# STRWL-S04-V00-Microcontroller.net
KiCad netlist of a schematic drawn in Altium Designer
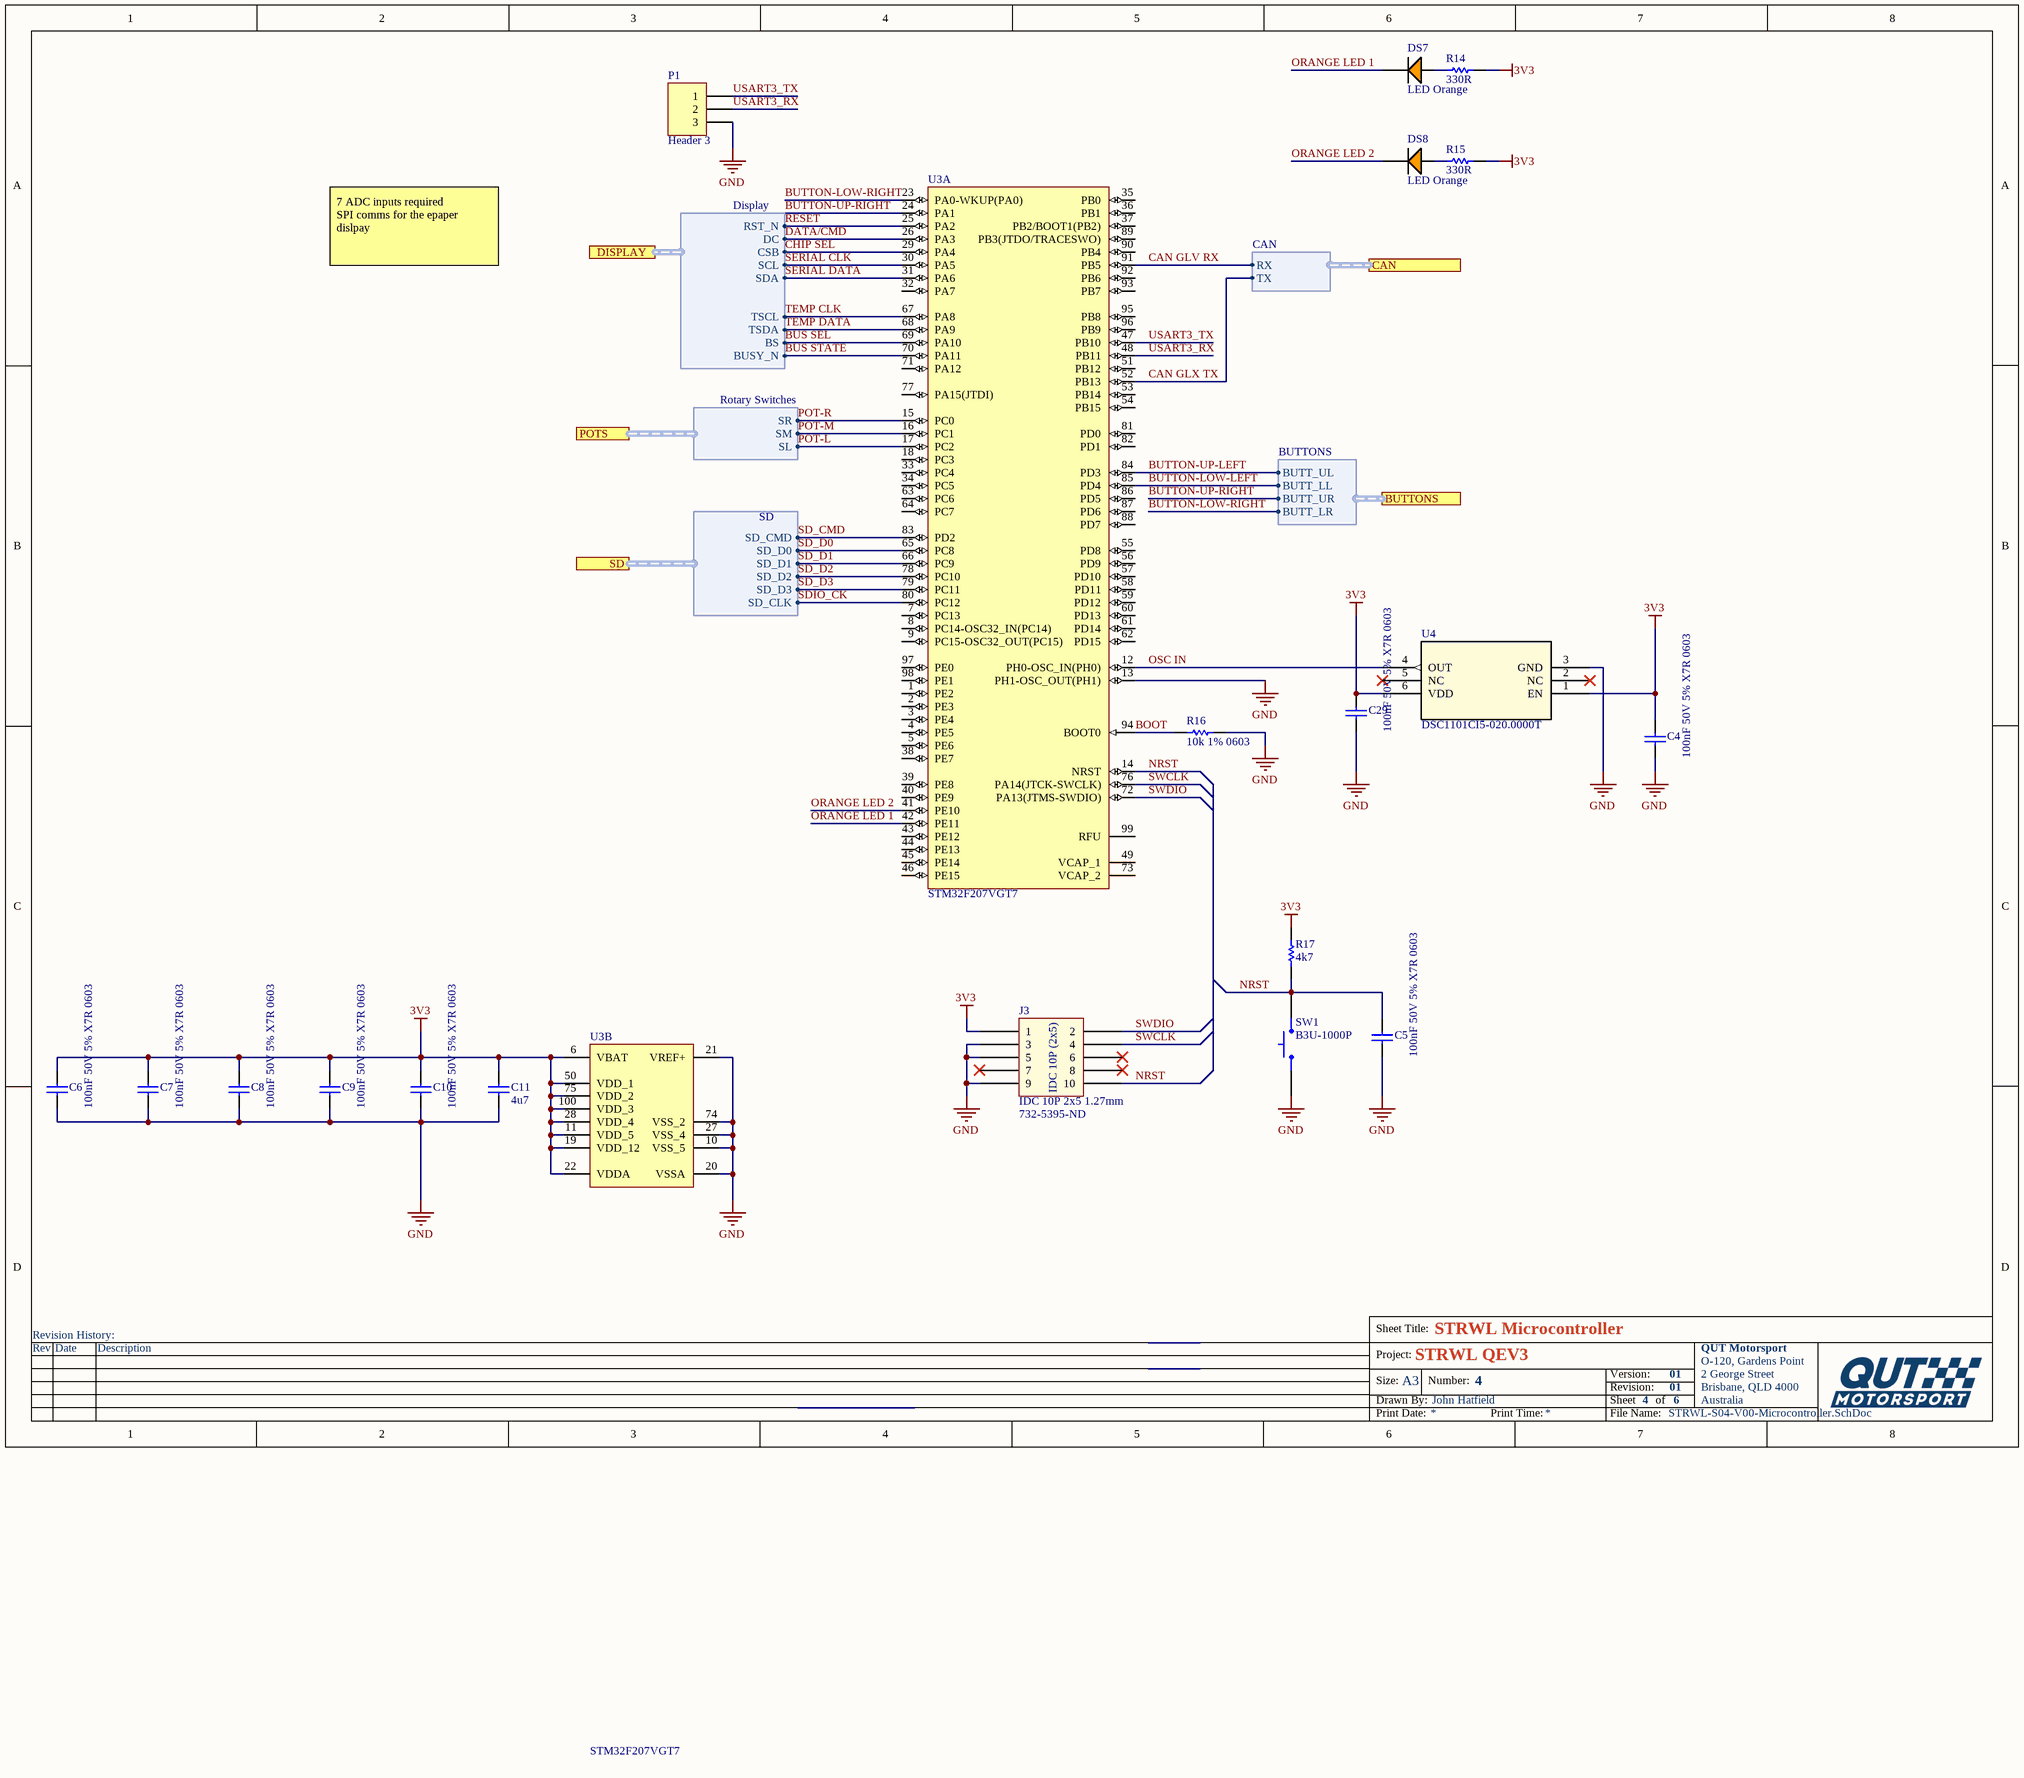
[diagram p0: STRWL-S04-V00-Microcontroller.SchDoc]

(export (version "E")
  (design (tool "Eeschema 10.0.6"))
  (components
    (comp (ref "C4")
      (value "100nF 50V 5% X7R 0603")
      (footprint "Cap_Ceramic_0603")
      (description "Capacitor, Ceramic, SMD, 100nF, 50V, 5%, X7R, 0603")
      (libsource (lib "StandardCapacitors") (part "100nF 50V 5% X7R 0603"))
    )
    (comp (ref "C5")
      (value "100nF 50V 5% X7R 0603")
      (footprint "Cap_Ceramic_0603")
      (description "Capacitor, Ceramic, SMD, 100nF, 50V, 5%, X7R, 0603")
      (libsource (lib "StandardCapacitors") (part "100nF 50V 5% X7R 0603"))
    )
    (comp (ref "C6")
      (value "100nF 50V 5% X7R 0603")
      (footprint "Cap_Ceramic_0603")
      (description "Capacitor, Ceramic, SMD, 100nF, 50V, 5%, X7R, 0603")
      (libsource (lib "StandardCapacitors") (part "100nF 50V 5% X7R 0603"))
    )
    (comp (ref "C7")
      (value "100nF 50V 5% X7R 0603")
      (footprint "Cap_Ceramic_0603")
      (description "Capacitor, Ceramic, SMD, 100nF, 50V, 5%, X7R, 0603")
      (libsource (lib "StandardCapacitors") (part "100nF 50V 5% X7R 0603"))
    )
    (comp (ref "C8")
      (value "100nF 50V 5% X7R 0603")
      (footprint "Cap_Ceramic_0603")
      (description "Capacitor, Ceramic, SMD, 100nF, 50V, 5%, X7R, 0603")
      (libsource (lib "StandardCapacitors") (part "100nF 50V 5% X7R 0603"))
    )
    (comp (ref "C9")
      (value "100nF 50V 5% X7R 0603")
      (footprint "Cap_Ceramic_0603")
      (description "Capacitor, Ceramic, SMD, 100nF, 50V, 5%, X7R, 0603")
      (libsource (lib "StandardCapacitors") (part "100nF 50V 5% X7R 0603"))
    )
    (comp (ref "C10")
      (value "100nF 50V 5% X7R 0603")
      (footprint "Cap_Ceramic_0603")
      (description "Capacitor, Ceramic, SMD, 100nF, 50V, 5%, X7R, 0603")
      (libsource (lib "StandardCapacitors") (part "100nF 50V 5% X7R 0603"))
    )
    (comp (ref "C11")
      (value "4u7")
      (footprint "Cap_Ceramic_0603")
      (description "Capacitor, Ceramic, SMD, 4u7, 50V, 5%, X7R, 0603")
      (libsource (lib "StandardCapacitors") (part "4u7 50V 5% X7R 0603"))
    )
    (comp (ref "C29")
      (value "100nF 50V 5% X7R 0603")
      (footprint "Cap_Ceramic_0603")
      (description "Capacitor, Ceramic, SMD, 100nF, 50V, 5%, X7R, 0603")
      (libsource (lib "StandardCapacitors") (part "100nF 50V 5% X7R 0603"))
    )
    (comp (ref "DS7")
      (value "LED Orange")
      (footprint "LED ORANGE 0603")
      (libsource (lib "QUTMS_LEDLibrary") (part "LED ORANGE 0603"))
    )
    (comp (ref "DS8")
      (value "LED Orange")
      (footprint "LED ORANGE 0603")
      (libsource (lib "QUTMS_LEDLibrary") (part "LED ORANGE 0603"))
    )
    (comp (ref "J3")
      (value "IDC 10P 2x5 1.27mm")
      (footprint "IDC 1.27MM 10P")
      (libsource (lib "IDCConnectors") (part "IDC 10P 2x5 1.27mm"))
    )
    (comp (ref "P1")
      (value "Header 3")
      (footprint "HDR1X3")
      (description "Header, 3-Pin")
      (fields (field (name "PUBLISHER") "Altium Limited"))
      (libsource (lib "Miscellaneous Connectors") (part "Header 3"))
    )
    (comp (ref "R14")
      (value "330R")
      (footprint "Res_ThinFilm_0603")
      (description "Resistor, SMD, 330R, 0.1W, 5%, 0603")
      (libsource (lib "StandardResistors") (part "330R 5% 0603"))
    )
    (comp (ref "R15")
      (value "330R")
      (footprint "Res_ThinFilm_0603")
      (description "Resistor, SMD, 330R, 0.1W, 5%, 0603")
      (libsource (lib "StandardResistors") (part "330R 5% 0603"))
    )
    (comp (ref "R16")
      (value "10k 1% 0603")
      (footprint "Res_ThinFilm_0603")
      (description "Resistor, SMD, 20k, 0.1W, 5%, 0603")
      (libsource (lib "QUTMS-MCISOLibrary") (part "20k 1% 0603"))
    )
    (comp (ref "R17")
      (value "4k7")
      (footprint "Res_ThinFilm_0603")
      (description "Resistor, SMD, 4k7, 0.1W, 5%, 0603")
      (libsource (lib "StandardResistors") (part "4k7 5% 0603"))
    )
    (comp (ref "SW1")
      (value "B3U-1000P")
      (footprint "BTN B3U-1000P")
      (description "Omron B3U-1000P Ultra Miniture Switch")
      (libsource (lib "QUTMS_SwitchLibrary") (part "BTN B3U-1000P"))
    )
    (comp (ref "U3")
      (value "STM32F207VGT7")
      (footprint "STM-LQFP100_N")
      (libsource (lib "STM32F207VGT7") (part "STM32F207VGT7-Custom"))
    )
    (comp (ref "U4")
      (value "DSC1101CI5-020.0000T")
      (footprint "VDFN6_3P2X2P5_MCH")
      (description "No Description Available")
      (fields (field (name "COPYRIGHT") "Copyright (C) 2018 Accelerated Designs. All rights reserved"))
      (libsource (lib "DSC1101CI5-020.0000T") (part "DSC1101CI5-020.0000T"))
    )
  )
  (nets
    (net (code "7") (name "/BOOT") (class "Default")
      (node (ref "R16") (pin "1") (pinfunction "1_1") (pintype "passive"))
      (node (ref "U3") (pin "94") (pinfunction "BOOT0_94") (pintype "input"))
    )
    (net (code "8") (name "/BUS SEL") (class "Default")
      (node (ref "U3") (pin "69") (pinfunction "PA10_69") (pintype "bidirectional"))
    )
    (net (code "9") (name "/BUS STATE") (class "Default")
      (node (ref "U3") (pin "70") (pinfunction "PA11_70") (pintype "bidirectional"))
    )
    (net (code "10") (name "/BUTTON-LOW-LEFT") (class "Default")
      (node (ref "U3") (pin "85") (pinfunction "PD4_85") (pintype "bidirectional"))
    )
    (net (code "11") (name "/BUTTON-LOW-RIGHT") (class "Default")
      (node (ref "U3") (pin "23") (pinfunction "PA0-WKUP(PA0)_23") (pintype "bidirectional"))
    )
    (net (code "12") (name "/BUTTON-UP-LEFT") (class "Default")
      (node (ref "U3") (pin "84") (pinfunction "PD3_84") (pintype "bidirectional"))
    )
    (net (code "13") (name "/BUTTON-UP-RIGHT") (class "Default")
      (node (ref "U3") (pin "24") (pinfunction "PA1_24") (pintype "bidirectional"))
    )
    (net (code "14") (name "/CAN GLV RX") (class "Default")
      (node (ref "U3") (pin "91") (pinfunction "PB5_91") (pintype "bidirectional"))
    )
    (net (code "15") (name "/CAN GLX TX") (class "Default")
      (node (ref "U3") (pin "52") (pinfunction "PB13_52") (pintype "bidirectional"))
    )
    (net (code "16") (name "/CHIP SEL") (class "Default")
      (node (ref "U3") (pin "29") (pinfunction "PA4_29") (pintype "bidirectional"))
    )
    (net (code "17") (name "/DATA{slash}CMD") (class "Default")
      (node (ref "U3") (pin "26") (pinfunction "PA3_26") (pintype "bidirectional"))
    )
    (net (code "18") (name "/NRST") (class "Default")
      (node (ref "C5") (pin "2") (pinfunction "2_2") (pintype "passive"))
      (node (ref "J3") (pin "10") (pinfunction "10_10") (pintype "passive"))
      (node (ref "R17") (pin "1") (pinfunction "1_1") (pintype "passive"))
      (node (ref "SW1") (pin "2") (pinfunction "2_2") (pintype "passive"))
      (node (ref "U3") (pin "14") (pinfunction "NRST_14") (pintype "bidirectional"))
    )
    (net (code "19") (name "/ORANGE LED 1") (class "Default")
      (node (ref "DS7") (pin "2") (pinfunction "C_2") (pintype "passive"))
      (node (ref "U3") (pin "42") (pinfunction "PE11_42") (pintype "bidirectional"))
    )
    (net (code "20") (name "/ORANGE LED 2") (class "Default")
      (node (ref "DS8") (pin "2") (pinfunction "C_2") (pintype "passive"))
      (node (ref "U3") (pin "41") (pinfunction "PE10_41") (pintype "bidirectional"))
    )
    (net (code "21") (name "/OSC IN") (class "Default")
      (node (ref "U3") (pin "12") (pinfunction "PH0-OSC_IN(PH0)_12") (pintype "bidirectional"))
      (node (ref "U4") (pin "4") (pinfunction "OUT_4") (pintype "output"))
    )
    (net (code "22") (name "/POT-L") (class "Default")
      (node (ref "U3") (pin "17") (pinfunction "PC2_17") (pintype "bidirectional"))
    )
    (net (code "23") (name "/POT-M") (class "Default")
      (node (ref "U3") (pin "16") (pinfunction "PC1_16") (pintype "bidirectional"))
    )
    (net (code "24") (name "/POT-R") (class "Default")
      (node (ref "U3") (pin "15") (pinfunction "PC0_15") (pintype "bidirectional"))
    )
    (net (code "25") (name "/RESET") (class "Default")
      (node (ref "U3") (pin "25") (pinfunction "PA2_25") (pintype "bidirectional"))
    )
    (net (code "26") (name "/SDIO_CK") (class "Default")
      (node (ref "U3") (pin "80") (pinfunction "PC12_80") (pintype "bidirectional"))
    )
    (net (code "27") (name "/SD_CMD") (class "Default")
      (node (ref "U3") (pin "83") (pinfunction "PD2_83") (pintype "bidirectional"))
    )
    (net (code "28") (name "/SD_D0") (class "Default")
      (node (ref "U3") (pin "65") (pinfunction "PC8_65") (pintype "bidirectional"))
    )
    (net (code "29") (name "/SD_D1") (class "Default")
      (node (ref "U3") (pin "66") (pinfunction "PC9_66") (pintype "bidirectional"))
    )
    (net (code "30") (name "/SD_D2") (class "Default")
      (node (ref "U3") (pin "78") (pinfunction "PC10_78") (pintype "bidirectional"))
    )
    (net (code "31") (name "/SD_D3") (class "Default")
      (node (ref "U3") (pin "79") (pinfunction "PC11_79") (pintype "bidirectional"))
    )
    (net (code "32") (name "/SERIAL CLK") (class "Default")
      (node (ref "U3") (pin "30") (pinfunction "PA5_30") (pintype "bidirectional"))
    )
    (net (code "33") (name "/SERIAL DATA") (class "Default")
      (node (ref "U3") (pin "31") (pinfunction "PA6_31") (pintype "bidirectional"))
    )
    (net (code "34") (name "/SWCLK") (class "Default")
      (node (ref "J3") (pin "4") (pinfunction "4_4") (pintype "passive"))
      (node (ref "U3") (pin "76") (pinfunction "PA14(JTCK-SWCLK)_76") (pintype "bidirectional"))
    )
    (net (code "35") (name "/SWDIO") (class "Default")
      (node (ref "J3") (pin "2") (pinfunction "2_2") (pintype "passive"))
      (node (ref "U3") (pin "72") (pinfunction "PA13(JTMS-SWDIO)_72") (pintype "bidirectional"))
    )
    (net (code "36") (name "/TEMP CLK") (class "Default")
      (node (ref "U3") (pin "67") (pinfunction "PA8_67") (pintype "bidirectional"))
    )
    (net (code "37") (name "/TEMP DATA") (class "Default")
      (node (ref "U3") (pin "68") (pinfunction "PA9_68") (pintype "bidirectional"))
    )
    (net (code "38") (name "/USART3_RX") (class "Default")
      (node (ref "P1") (pin "2") (pinfunction "2_2") (pintype "passive"))
      (node (ref "U3") (pin "48") (pinfunction "PB11_48") (pintype "bidirectional"))
    )
    (net (code "39") (name "/USART3_TX") (class "Default")
      (node (ref "P1") (pin "1") (pinfunction "1_1") (pintype "passive"))
      (node (ref "U3") (pin "47") (pinfunction "PB10_47") (pintype "bidirectional"))
    )
    (net (code "45") (name "3V3") (class "Default")
      (node (ref "C10") (pin "2") (pinfunction "2_2") (pintype "passive"))
      (node (ref "C11") (pin "2") (pinfunction "2_2") (pintype "passive"))
      (node (ref "C29") (pin "2") (pinfunction "2_2") (pintype "passive"))
      (node (ref "C4") (pin "2") (pinfunction "2_2") (pintype "passive"))
      (node (ref "C6") (pin "2") (pinfunction "2_2") (pintype "passive"))
      (node (ref "C7") (pin "2") (pinfunction "2_2") (pintype "passive"))
      (node (ref "C8") (pin "2") (pinfunction "2_2") (pintype "passive"))
      (node (ref "C9") (pin "2") (pinfunction "2_2") (pintype "passive"))
      (node (ref "J3") (pin "1") (pinfunction "1_1") (pintype "passive"))
      (node (ref "R14") (pin "2") (pinfunction "2_2") (pintype "passive"))
      (node (ref "R15") (pin "2") (pinfunction "2_2") (pintype "passive"))
      (node (ref "R17") (pin "2") (pinfunction "2_2") (pintype "passive"))
      (node (ref "U3") (pin "100") (pinfunction "VDD_3_100") (pintype "power_in"))
      (node (ref "U3") (pin "11") (pinfunction "VDD_5_11") (pintype "power_in"))
      (node (ref "U3") (pin "19") (pinfunction "VDD_12_19") (pintype "power_in"))
      (node (ref "U3") (pin "22") (pinfunction "VDDA_22") (pintype "power_in"))
      (node (ref "U3") (pin "28") (pinfunction "VDD_4_28") (pintype "power_in"))
      (node (ref "U3") (pin "50") (pinfunction "VDD_1_50") (pintype "power_in"))
      (node (ref "U3") (pin "6") (pinfunction "VBAT_6") (pintype "power_in"))
      (node (ref "U3") (pin "75") (pinfunction "VDD_2_75") (pintype "power_in"))
      (node (ref "U4") (pin "1") (pinfunction "EN_1") (pintype "passive"))
      (node (ref "U4") (pin "6") (pinfunction "VDD_6") (pintype "power_in"))
    )
    (net (code "46") (name "GND") (class "Default")
      (node (ref "C10") (pin "1") (pinfunction "1_1") (pintype "passive"))
      (node (ref "C11") (pin "1") (pinfunction "1_1") (pintype "passive"))
      (node (ref "C29") (pin "1") (pinfunction "1_1") (pintype "passive"))
      (node (ref "C4") (pin "1") (pinfunction "1_1") (pintype "passive"))
      (node (ref "C5") (pin "1") (pinfunction "1_1") (pintype "passive"))
      (node (ref "C6") (pin "1") (pinfunction "1_1") (pintype "passive"))
      (node (ref "C7") (pin "1") (pinfunction "1_1") (pintype "passive"))
      (node (ref "C8") (pin "1") (pinfunction "1_1") (pintype "passive"))
      (node (ref "C9") (pin "1") (pinfunction "1_1") (pintype "passive"))
      (node (ref "J3") (pin "3") (pinfunction "3_3") (pintype "passive"))
      (node (ref "J3") (pin "5") (pinfunction "5_5") (pintype "passive"))
      (node (ref "J3") (pin "9") (pinfunction "9_9") (pintype "passive"))
      (node (ref "P1") (pin "3") (pinfunction "3_3") (pintype "passive"))
      (node (ref "R16") (pin "2") (pinfunction "2_2") (pintype "passive"))
      (node (ref "SW1") (pin "1") (pinfunction "1_1") (pintype "passive"))
      (node (ref "U3") (pin "10") (pinfunction "VSS_5_10") (pintype "power_in"))
      (node (ref "U3") (pin "13") (pinfunction "PH1-OSC_OUT(PH1)_13") (pintype "bidirectional"))
      (node (ref "U3") (pin "20") (pinfunction "VSSA_20") (pintype "power_in"))
      (node (ref "U3") (pin "21") (pinfunction "VREF+_21") (pintype "power_in"))
      (node (ref "U3") (pin "27") (pinfunction "VSS_4_27") (pintype "power_in"))
      (node (ref "U3") (pin "74") (pinfunction "VSS_2_74") (pintype "power_in"))
      (node (ref "U4") (pin "3") (pinfunction "GND_3") (pintype "passive"))
    )
    (net (code "47") (name "Net-(DS7-A)") (class "Default")
      (node (ref "DS7") (pin "1") (pinfunction "A_1") (pintype "passive"))
      (node (ref "R14") (pin "1") (pinfunction "1_1") (pintype "passive"))
    )
    (net (code "48") (name "Net-(DS8-A)") (class "Default")
      (node (ref "DS8") (pin "1") (pinfunction "A_1") (pintype "passive"))
      (node (ref "R15") (pin "1") (pinfunction "1_1") (pintype "passive"))
    )
    (net (code "49") (name "unconnected-(J3-Pad6)") (class "Default")
      (node (ref "J3") (pin "6") (pinfunction "6_6") (pintype "passive+no_connect"))
    )
    (net (code "50") (name "unconnected-(J3-Pad7)") (class "Default")
      (node (ref "J3") (pin "7") (pinfunction "7_7") (pintype "passive+no_connect"))
    )
    (net (code "51") (name "unconnected-(J3-Pad8)") (class "Default")
      (node (ref "J3") (pin "8") (pinfunction "8_8") (pintype "passive+no_connect"))
    )
    (net (code "52") (name "unconnected-(U3A-PA7-Pad32)") (class "Default")
      (node (ref "U3") (pin "32") (pinfunction "PA7_32") (pintype "bidirectional"))
    )
    (net (code "53") (name "unconnected-(U3A-PA12-Pad71)") (class "Default")
      (node (ref "U3") (pin "71") (pinfunction "PA12_71") (pintype "bidirectional"))
    )
    (net (code "54") (name "unconnected-(U3A-PA15(JTDI)-Pad77)") (class "Default")
      (node (ref "U3") (pin "77") (pinfunction "PA15(JTDI)_77") (pintype "bidirectional"))
    )
    (net (code "55") (name "unconnected-(U3A-PB0-Pad35)") (class "Default")
      (node (ref "U3") (pin "35") (pinfunction "PB0_35") (pintype "bidirectional"))
    )
    (net (code "56") (name "unconnected-(U3A-PB1-Pad36)") (class "Default")
      (node (ref "U3") (pin "36") (pinfunction "PB1_36") (pintype "bidirectional"))
    )
    (net (code "57") (name "unconnected-(U3A-PB2{slash}BOOT1(PB2)-Pad37)") (class "Default")
      (node (ref "U3") (pin "37") (pinfunction "PB2/BOOT1(PB2)_37") (pintype "bidirectional"))
    )
    (net (code "58") (name "unconnected-(U3A-PB3(JTDO{slash}TRACESWO)-Pad89)") (class "Default")
      (node (ref "U3") (pin "89") (pinfunction "PB3(JTDO/TRACESWO)_89") (pintype "bidirectional"))
    )
    (net (code "59") (name "unconnected-(U3A-PB4-Pad90)") (class "Default")
      (node (ref "U3") (pin "90") (pinfunction "PB4_90") (pintype "bidirectional"))
    )
    (net (code "60") (name "unconnected-(U3A-PB6-Pad92)") (class "Default")
      (node (ref "U3") (pin "92") (pinfunction "PB6_92") (pintype "bidirectional"))
    )
    (net (code "61") (name "unconnected-(U3A-PB7-Pad93)") (class "Default")
      (node (ref "U3") (pin "93") (pinfunction "PB7_93") (pintype "bidirectional"))
    )
    (net (code "62") (name "unconnected-(U3A-PB8-Pad95)") (class "Default")
      (node (ref "U3") (pin "95") (pinfunction "PB8_95") (pintype "bidirectional"))
    )
    (net (code "63") (name "unconnected-(U3A-PB9-Pad96)") (class "Default")
      (node (ref "U3") (pin "96") (pinfunction "PB9_96") (pintype "bidirectional"))
    )
    (net (code "64") (name "unconnected-(U3A-PB12-Pad51)") (class "Default")
      (node (ref "U3") (pin "51") (pinfunction "PB12_51") (pintype "bidirectional"))
    )
    (net (code "65") (name "unconnected-(U3A-PB14-Pad53)") (class "Default")
      (node (ref "U3") (pin "53") (pinfunction "PB14_53") (pintype "bidirectional"))
    )
    (net (code "66") (name "unconnected-(U3A-PB15-Pad54)") (class "Default")
      (node (ref "U3") (pin "54") (pinfunction "PB15_54") (pintype "bidirectional"))
    )
    (net (code "67") (name "unconnected-(U3A-PC3-Pad18)") (class "Default")
      (node (ref "U3") (pin "18") (pinfunction "PC3_18") (pintype "bidirectional"))
    )
    (net (code "68") (name "unconnected-(U3A-PC4-Pad33)") (class "Default")
      (node (ref "U3") (pin "33") (pinfunction "PC4_33") (pintype "bidirectional"))
    )
    (net (code "69") (name "unconnected-(U3A-PC5-Pad34)") (class "Default")
      (node (ref "U3") (pin "34") (pinfunction "PC5_34") (pintype "bidirectional"))
    )
    (net (code "70") (name "unconnected-(U3A-PC6-Pad63)") (class "Default")
      (node (ref "U3") (pin "63") (pinfunction "PC6_63") (pintype "bidirectional"))
    )
    (net (code "71") (name "unconnected-(U3A-PC7-Pad64)") (class "Default")
      (node (ref "U3") (pin "64") (pinfunction "PC7_64") (pintype "bidirectional"))
    )
    (net (code "72") (name "unconnected-(U3A-PC13-Pad7)") (class "Default")
      (node (ref "U3") (pin "7") (pinfunction "PC13_7") (pintype "bidirectional"))
    )
    (net (code "73") (name "unconnected-(U3A-PC14-OSC32_IN(PC14)-Pad8)") (class "Default")
      (node (ref "U3") (pin "8") (pinfunction "PC14-OSC32_IN(PC14)_8") (pintype "bidirectional"))
    )
    (net (code "74") (name "unconnected-(U3A-PC15-OSC32_OUT(PC15)-Pad9)") (class "Default")
      (node (ref "U3") (pin "9") (pinfunction "PC15-OSC32_OUT(PC15)_9") (pintype "bidirectional"))
    )
    (net (code "75") (name "unconnected-(U3A-PD0-Pad81)") (class "Default")
      (node (ref "U3") (pin "81") (pinfunction "PD0_81") (pintype "bidirectional"))
    )
    (net (code "76") (name "unconnected-(U3A-PD1-Pad82)") (class "Default")
      (node (ref "U3") (pin "82") (pinfunction "PD1_82") (pintype "bidirectional"))
    )
    (net (code "77") (name "unconnected-(U3A-PD5-Pad86)") (class "Default")
      (node (ref "U3") (pin "86") (pinfunction "PD5_86") (pintype "bidirectional"))
    )
    (net (code "78") (name "unconnected-(U3A-PD6-Pad87)") (class "Default")
      (node (ref "U3") (pin "87") (pinfunction "PD6_87") (pintype "bidirectional"))
    )
    (net (code "79") (name "unconnected-(U3A-PD7-Pad88)") (class "Default")
      (node (ref "U3") (pin "88") (pinfunction "PD7_88") (pintype "bidirectional"))
    )
    (net (code "80") (name "unconnected-(U3A-PD8-Pad55)") (class "Default")
      (node (ref "U3") (pin "55") (pinfunction "PD8_55") (pintype "bidirectional"))
    )
    (net (code "81") (name "unconnected-(U3A-PD9-Pad56)") (class "Default")
      (node (ref "U3") (pin "56") (pinfunction "PD9_56") (pintype "bidirectional"))
    )
    (net (code "82") (name "unconnected-(U3A-PD10-Pad57)") (class "Default")
      (node (ref "U3") (pin "57") (pinfunction "PD10_57") (pintype "bidirectional"))
    )
    (net (code "83") (name "unconnected-(U3A-PD11-Pad58)") (class "Default")
      (node (ref "U3") (pin "58") (pinfunction "PD11_58") (pintype "bidirectional"))
    )
    (net (code "84") (name "unconnected-(U3A-PD12-Pad59)") (class "Default")
      (node (ref "U3") (pin "59") (pinfunction "PD12_59") (pintype "bidirectional"))
    )
    (net (code "85") (name "unconnected-(U3A-PD13-Pad60)") (class "Default")
      (node (ref "U3") (pin "60") (pinfunction "PD13_60") (pintype "bidirectional"))
    )
    (net (code "86") (name "unconnected-(U3A-PD14-Pad61)") (class "Default")
      (node (ref "U3") (pin "61") (pinfunction "PD14_61") (pintype "bidirectional"))
    )
    (net (code "87") (name "unconnected-(U3A-PD15-Pad62)") (class "Default")
      (node (ref "U3") (pin "62") (pinfunction "PD15_62") (pintype "bidirectional"))
    )
    (net (code "88") (name "unconnected-(U3A-PE0-Pad97)") (class "Default")
      (node (ref "U3") (pin "97") (pinfunction "PE0_97") (pintype "bidirectional"))
    )
    (net (code "89") (name "unconnected-(U3A-PE1-Pad98)") (class "Default")
      (node (ref "U3") (pin "98") (pinfunction "PE1_98") (pintype "bidirectional"))
    )
    (net (code "90") (name "unconnected-(U3A-PE2-Pad1)") (class "Default")
      (node (ref "U3") (pin "1") (pinfunction "PE2_1") (pintype "bidirectional"))
    )
    (net (code "91") (name "unconnected-(U3A-PE3-Pad2)") (class "Default")
      (node (ref "U3") (pin "2") (pinfunction "PE3_2") (pintype "bidirectional"))
    )
    (net (code "92") (name "unconnected-(U3A-PE4-Pad3)") (class "Default")
      (node (ref "U3") (pin "3") (pinfunction "PE4_3") (pintype "bidirectional"))
    )
    (net (code "93") (name "unconnected-(U3A-PE5-Pad4)") (class "Default")
      (node (ref "U3") (pin "4") (pinfunction "PE5_4") (pintype "bidirectional"))
    )
    (net (code "94") (name "unconnected-(U3A-PE6-Pad5)") (class "Default")
      (node (ref "U3") (pin "5") (pinfunction "PE6_5") (pintype "bidirectional"))
    )
    (net (code "95") (name "unconnected-(U3A-PE7-Pad38)") (class "Default")
      (node (ref "U3") (pin "38") (pinfunction "PE7_38") (pintype "bidirectional"))
    )
    (net (code "96") (name "unconnected-(U3A-PE8-Pad39)") (class "Default")
      (node (ref "U3") (pin "39") (pinfunction "PE8_39") (pintype "bidirectional"))
    )
    (net (code "97") (name "unconnected-(U3A-PE9-Pad40)") (class "Default")
      (node (ref "U3") (pin "40") (pinfunction "PE9_40") (pintype "bidirectional"))
    )
    (net (code "98") (name "unconnected-(U3A-PE12-Pad43)") (class "Default")
      (node (ref "U3") (pin "43") (pinfunction "PE12_43") (pintype "bidirectional"))
    )
    (net (code "99") (name "unconnected-(U3A-PE13-Pad44)") (class "Default")
      (node (ref "U3") (pin "44") (pinfunction "PE13_44") (pintype "bidirectional"))
    )
    (net (code "100") (name "unconnected-(U3A-PE14-Pad45)") (class "Default")
      (node (ref "U3") (pin "45") (pinfunction "PE14_45") (pintype "bidirectional"))
    )
    (net (code "101") (name "unconnected-(U3A-PE15-Pad46)") (class "Default")
      (node (ref "U3") (pin "46") (pinfunction "PE15_46") (pintype "bidirectional"))
    )
    (net (code "102") (name "unconnected-(U3A-RFU-Pad99)") (class "Default")
      (node (ref "U3") (pin "99") (pinfunction "RFU_99") (pintype "passive"))
    )
    (net (code "103") (name "unconnected-(U3A-VCAP_1-Pad49)") (class "Default")
      (node (ref "U3") (pin "49") (pinfunction "VCAP_1_49") (pintype "power_in"))
    )
    (net (code "104") (name "unconnected-(U3A-VCAP_2-Pad73)") (class "Default")
      (node (ref "U3") (pin "73") (pinfunction "VCAP_2_73") (pintype "power_in"))
    )
    (net (code "105") (name "unconnected-(U4-NC-Pad2)") (class "Default")
      (node (ref "U4") (pin "2") (pinfunction "NC_2") (pintype "passive+no_connect"))
    )
    (net (code "106") (name "unconnected-(U4-NC-Pad5)") (class "Default")
      (node (ref "U4") (pin "5") (pinfunction "NC_5") (pintype "passive+no_connect"))
    )
  )
)
